# SensorSheet.net
KiCad netlist of a schematic drawn in Altium Designer
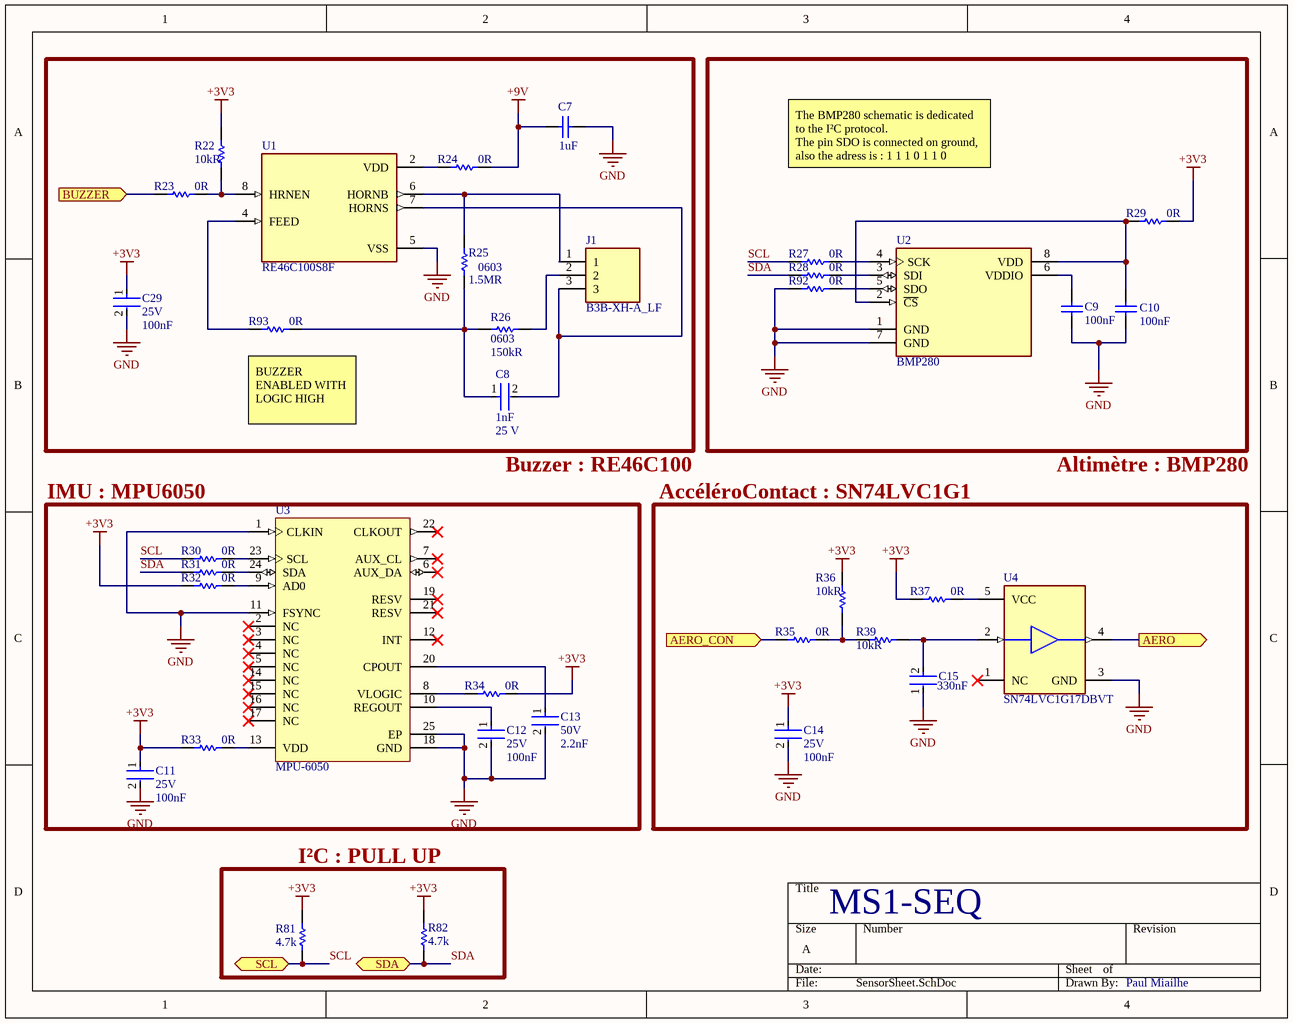
[diagram p0: SensorSheet.SchDoc]

(export (version "E")
  (design (tool "Eeschema 10.0.6"))
  (components
    (comp (ref "C7")
      (value "GRM188R61E105KA12D")
      (footprint "CAPC1608X90X35LL10T15")
      (fields
        (field (name "MANUFACTURER") "Murata")
        (field (name "CAPACITANCE") "1uF")
        (field (name "TOLERANCE") "10%")
        (field (name "VOLTAGE") "25V")
      )
      (libsource (lib "Altium Content Vault") (part "CAP"))
    )
    (comp (ref "C8")
      (value "C0603C102J3GACTU")
      (footprint "FP-C0603C-CF-MFG")
      (description "CAP CER 1000PF 25V 5% NP0 0603")
      (fields
        (field (name "OCTOPART") "https://octopart.com/c0603c102j3gactu-kemet-8375722")
        (field (name "CAPACITANCE") "1nF")
        (field (name "TOLERANCE") "0.05")
        (field (name "VOLTAGE RATING") "25 V")
      )
      (libsource (lib "Altium Content Vault") (part "b4654b650e69147ec39a6b967a45e02"))
    )
    (comp (ref "C9")
      (value "100nF")
      (footprint "SAMS-C0603-2_M")
      (description "Multi-layer Ceramic Capacitor, -55 to 125 degC, 2-Pin SMD (0603), RoHS, Tape and Reel")
      (fields (field (name "MANUFACTURER") "Samsung Electro-Mechanics"))
      (libsource (lib "Altium Content Vault") (part "CAP-NP-2"))
    )
    (comp (ref "C10")
      (value "100nF")
      (footprint "SAMS-C0603-2_M")
      (description "Multi-layer Ceramic Capacitor, -55 to 125 degC, 2-Pin SMD (0603), RoHS, Tape and Reel")
      (fields (field (name "MANUFACTURER") "Samsung Electro-Mechanics"))
      (libsource (lib "Altium Content Vault") (part "CAP-NP-2"))
    )
    (comp (ref "C11")
      (value "CGA3E2X7R1E104K080AA")
      (footprint "FP-CGA3E-0_3-0_1-MFG")
      (description "Cap Ceramic 100nF 25V X7R 10% Pad SMD 0603 +125°C Automotive T/R")
      (fields
        (field (name "VOLTAGE RATING (DC)") "25V")
        (field (name "CAPACITANCE") "100nF")
        (field (name "TOLERANCE") "10%")
        (field (name "MANUFACTURER") "TDK")
      )
      (libsource (lib "Altium Content Vault") (part "b4654b650e69147ec39a6b967a45e02"))
    )
    (comp (ref "C12")
      (value "CGA3E2X7R1E104K080AA")
      (footprint "FP-CGA3E-0_3-0_1-MFG")
      (description "Cap Ceramic 100nF 25V X7R 10% Pad SMD 0603 +125°C Automotive T/R")
      (fields
        (field (name "VOLTAGE RATING (DC)") "25V")
        (field (name "CAPACITANCE") "100nF")
        (field (name "TOLERANCE") "10%")
        (field (name "MANUFACTURER") "TDK")
      )
      (libsource (lib "Altium Content Vault") (part "b4654b650e69147ec39a6b967a45e02"))
    )
    (comp (ref "C13")
      (value "GRM1885C1H222JA01D")
      (footprint "FP-GRM188-0_1-e0_2_0_5-MFG")
      (description "Chip Multilayer Ceramic Capacitors for General Purpose, 0603, 2200pF, C0G, 30ppm/°C, 5%, 50V")
      (fields
        (field (name "VOLTAGE") "50V")
        (field (name "TOLERANCE") "5%")
        (field (name "CAPACITANCE") "2.2nF")
        (field (name "MANUFACTURER") "Murata")
      )
      (libsource (lib "Altium Content Vault") (part "11868f565c42a9108669ba33697ecf6"))
    )
    (comp (ref "C14")
      (value "CGA3E2X7R1E104K080AA")
      (footprint "FP-CGA3E-0_3-0_1-MFG")
      (description "Cap Ceramic 100nF 25V X7R 10% Pad SMD 0603 +125°C Automotive T/R")
      (fields
        (field (name "VOLTAGE RATING (DC)") "25V")
        (field (name "CAPACITANCE") "100nF")
        (field (name "TOLERANCE") "10%")
        (field (name "MANUFACTURER") "TDK")
      )
      (libsource (lib "Altium Content Vault") (part "b4654b650e69147ec39a6b967a45e02"))
    )
    (comp (ref "C15")
      (value "C1608X7R1H334K080AC")
      (footprint "FP-C1608-080-0_1-IPC_B")
      (description "Multilayer Ceramic Capacitors 330nF ±10% 50V X7R SMD 0603")
      (fields
        (field (name "CAPACITANCE") "330nF")
        (field (name "TOLERANCE") "10%")
        (field (name "VOLTAGE") "50V")
      )
      (libsource (lib "Altium Content Vault") (part "236180d848d6139a670b325ea6854c9"))
    )
    (comp (ref "C29")
      (value "CGA3E2X7R1E104K080AA")
      (footprint "FP-CGA3E-0_3-0_1-MFG")
      (description "Cap Ceramic 100nF 25V X7R 10% Pad SMD 0603 +125°C Automotive T/R")
      (fields
        (field (name "VOLTAGE RATING (DC)") "25V")
        (field (name "CAPACITANCE") "100nF")
        (field (name "TOLERANCE") "10%")
        (field (name "MANUFACTURER") "TDK")
      )
      (libsource (lib "Altium Content Vault") (part "b4654b650e69147ec39a6b967a45e02"))
    )
    (comp (ref "J1")
      (value "B3B-XH-A_LF")
      (footprint "SamacSys:B3BXHALFSN")
      (description "Connector")
      (fields (field (name "MANUFACTURER_PART_NUMBER") "B3B-XH-A(LF)(SN)"))
      (libsource (lib "*") (part "B3B-XH-A_LF__SN_"))
    )
    (comp (ref "R22")
      (value "ERJ3EKF1002V")
      (footprint "RESC1609X55X30LL15T15")
      (description "Chip Resistor, 10 KOhm, +/- 1%, 0.1 W, -55 to 155 degC, 0603 (1608 Metric), RoHS, Tape and Reel")
      (fields
        (field (name "RESISTANCE") "10kR")
        (field (name "TOLERANCE") "1%")
        (field (name "MANUFACTURER") "Panasonic")
      )
      (libsource (lib "Altium Content Vault") (part "RES-2"))
    )
    (comp (ref "R23")
      (value "0R")
      (footprint "RESC1608X55X25ML10T15")
      (description "Chip Resistor, 0 Ohm, +/- 5%, 0.1 W, -55 to 155 degC, 0603 (1608 Metric), RoHS, Tape and Reel")
      (fields (field (name "TOLERANCE") "5%") (field (name "MANUFACTURER") "Yageo"))
      (libsource (lib "Altium Content Vault") (part "RES-2"))
    )
    (comp (ref "R24")
      (value "0R")
      (footprint "RESC1608X55X25ML10T15")
      (description "Chip Resistor, 0 Ohm, +/- 5%, 0.1 W, -55 to 155 degC, 0603 (1608 Metric), RoHS, Tape and Reel")
      (fields (field (name "TOLERANCE") "5%") (field (name "MANUFACTURER") "Yageo"))
      (libsource (lib "Altium Content Vault") (part "RES-2"))
    )
    (comp (ref "R25")
      (value "ERJ-3GEYJ155V")
      (footprint "RESC1608X55X30ML15T15")
      (fields
        (field (name "MANUFACTURER") "Panasonic")
        (field (name "CASE CODE (IMPERIAL)") "0603")
        (field (name "RESISTANCE") "1.5MR")
        (field (name "TOLERANCE") "5%")
      )
      (libsource (lib "Altium Content Vault") (part "RES"))
    )
    (comp (ref "R26")
      (value "ERJ-3EKF1503V")
      (footprint "RESC1608X55X30NL15T15")
      (fields
        (field (name "MANUFACTURER") "Panasonic")
        (field (name "CASE CODE (IMPERIAL)") "0603")
        (field (name "RESISTANCE") "150kR")
        (field (name "TOLERANCE") "1%")
      )
      (libsource (lib "Altium Content Vault") (part "RES"))
    )
    (comp (ref "R27")
      (value "0R")
      (footprint "RESC1608X55X25ML10T15")
      (description "Chip Resistor, 0 Ohm, +/- 5%, 0.1 W, -55 to 155 degC, 0603 (1608 Metric), RoHS, Tape and Reel")
      (fields (field (name "TOLERANCE") "5%") (field (name "MANUFACTURER") "Yageo"))
      (libsource (lib "Altium Content Vault") (part "RES-2"))
    )
    (comp (ref "R28")
      (value "0R")
      (footprint "RESC1608X55X25ML10T15")
      (description "Chip Resistor, 0 Ohm, +/- 5%, 0.1 W, -55 to 155 degC, 0603 (1608 Metric), RoHS, Tape and Reel")
      (fields (field (name "TOLERANCE") "5%") (field (name "MANUFACTURER") "Yageo"))
      (libsource (lib "Altium Content Vault") (part "RES-2"))
    )
    (comp (ref "R29")
      (value "0R")
      (footprint "RESC1608X55X25ML10T15")
      (description "Chip Resistor, 0 Ohm, +/- 5%, 0.1 W, -55 to 155 degC, 0603 (1608 Metric), RoHS, Tape and Reel")
      (fields (field (name "TOLERANCE") "5%") (field (name "MANUFACTURER") "Yageo"))
      (libsource (lib "Altium Content Vault") (part "RES-2"))
    )
    (comp (ref "R30")
      (value "0R")
      (footprint "RESC1608X55X25ML10T15")
      (description "Chip Resistor, 0 Ohm, +/- 5%, 0.1 W, -55 to 155 degC, 0603 (1608 Metric), RoHS, Tape and Reel")
      (fields (field (name "TOLERANCE") "5%") (field (name "MANUFACTURER") "Yageo"))
      (libsource (lib "Altium Content Vault") (part "RES-2"))
    )
    (comp (ref "R31")
      (value "0R")
      (footprint "RESC1608X55X25ML10T15")
      (description "Chip Resistor, 0 Ohm, +/- 5%, 0.1 W, -55 to 155 degC, 0603 (1608 Metric), RoHS, Tape and Reel")
      (fields (field (name "TOLERANCE") "5%") (field (name "MANUFACTURER") "Yageo"))
      (libsource (lib "Altium Content Vault") (part "RES-2"))
    )
    (comp (ref "R32")
      (value "0R")
      (footprint "RESC1608X55X25ML10T15")
      (description "Chip Resistor, 0 Ohm, +/- 5%, 0.1 W, -55 to 155 degC, 0603 (1608 Metric), RoHS, Tape and Reel")
      (fields (field (name "TOLERANCE") "5%") (field (name "MANUFACTURER") "Yageo"))
      (libsource (lib "Altium Content Vault") (part "RES-2"))
    )
    (comp (ref "R33")
      (value "0R")
      (footprint "RESC1608X55X25ML10T15")
      (description "Chip Resistor, 0 Ohm, +/- 5%, 0.1 W, -55 to 155 degC, 0603 (1608 Metric), RoHS, Tape and Reel")
      (fields (field (name "TOLERANCE") "5%") (field (name "MANUFACTURER") "Yageo"))
      (libsource (lib "Altium Content Vault") (part "RES-2"))
    )
    (comp (ref "R34")
      (value "0R")
      (footprint "RESC1608X55X25ML10T15")
      (description "Chip Resistor, 0 Ohm, +/- 5%, 0.1 W, -55 to 155 degC, 0603 (1608 Metric), RoHS, Tape and Reel")
      (fields (field (name "TOLERANCE") "5%") (field (name "MANUFACTURER") "Yageo"))
      (libsource (lib "Altium Content Vault") (part "RES-2"))
    )
    (comp (ref "R35")
      (value "0R")
      (footprint "RESC1608X55X25ML10T15")
      (description "Chip Resistor, 0 Ohm, +/- 5%, 0.1 W, -55 to 155 degC, 0603 (1608 Metric), RoHS, Tape and Reel")
      (fields (field (name "TOLERANCE") "5%") (field (name "MANUFACTURER") "Yageo"))
      (libsource (lib "Altium Content Vault") (part "RES-2"))
    )
    (comp (ref "R36")
      (value "ERJ3EKF1002V")
      (footprint "RESC1609X55X30LL15T15")
      (description "Chip Resistor, 10 KOhm, +/- 1%, 0.1 W, -55 to 155 degC, 0603 (1608 Metric), RoHS, Tape and Reel")
      (fields
        (field (name "RESISTANCE") "10kR")
        (field (name "TOLERANCE") "1%")
        (field (name "MANUFACTURER") "Panasonic")
      )
      (libsource (lib "Altium Content Vault") (part "RES-2"))
    )
    (comp (ref "R37")
      (value "0R")
      (footprint "RESC1608X55X25ML10T15")
      (description "Chip Resistor, 0 Ohm, +/- 5%, 0.1 W, -55 to 155 degC, 0603 (1608 Metric), RoHS, Tape and Reel")
      (fields (field (name "TOLERANCE") "5%") (field (name "MANUFACTURER") "Yageo"))
      (libsource (lib "Altium Content Vault") (part "RES-2"))
    )
    (comp (ref "R39")
      (value "ERJ3EKF1002V")
      (footprint "RESC1609X55X30LL15T15")
      (description "Chip Resistor, 10 KOhm, +/- 1%, 0.1 W, -55 to 155 degC, 0603 (1608 Metric), RoHS, Tape and Reel")
      (fields
        (field (name "RESISTANCE") "10kR")
        (field (name "TOLERANCE") "1%")
        (field (name "MANUFACTURER") "Panasonic")
      )
      (libsource (lib "Altium Content Vault") (part "RES-2"))
    )
    (comp (ref "R81")
      (value "RC0603FR-074K7L")
      (footprint "RESC1608X55X25LL10T15")
      (description "Chip Resistor, 4.7 KOhm, +/- 1%, 0.1 W, -55 to 155 degC, 0603 (1608 Metric), RoHS, Tape and Reel")
      (fields
        (field (name "MANUFACTURER") "Yageo")
        (field (name "RESISTANCE") "4.7k")
        (field (name "TOLERANCE") "1%")
      )
      (libsource (lib "Altium Content Vault") (part "RES-2"))
    )
    (comp (ref "R82")
      (value "RC0603FR-074K7L")
      (footprint "RESC1608X55X25LL10T15")
      (description "Chip Resistor, 4.7 KOhm, +/- 1%, 0.1 W, -55 to 155 degC, 0603 (1608 Metric), RoHS, Tape and Reel")
      (fields
        (field (name "MANUFACTURER") "Yageo")
        (field (name "RESISTANCE") "4.7k")
        (field (name "TOLERANCE") "1%")
      )
      (libsource (lib "Altium Content Vault") (part "RES-2"))
    )
    (comp (ref "R92")
      (value "0R")
      (footprint "RESC1608X55X25ML10T15")
      (description "Chip Resistor, 0 Ohm, +/- 5%, 0.1 W, -55 to 155 degC, 0603 (1608 Metric), RoHS, Tape and Reel")
      (fields (field (name "TOLERANCE") "5%") (field (name "MANUFACTURER") "Yageo"))
      (libsource (lib "Altium Content Vault") (part "RES-2"))
    )
    (comp (ref "R93")
      (value "0R")
      (footprint "RESC1608X55X25ML10T15")
      (description "Chip Resistor, 0 Ohm, +/- 5%, 0.1 W, -55 to 155 degC, 0603 (1608 Metric), RoHS, Tape and Reel")
      (fields (field (name "TOLERANCE") "5%") (field (name "MANUFACTURER") "Yageo"))
      (libsource (lib "Altium Content Vault") (part "RES-2"))
    )
    (comp (ref "U1")
      (value "RE46C100S8F")
      (footprint "RE46C100S8F:SOIC127P600X175-8N")
      (fields (field (name "MF") "{'manufacturer': u'Microchip Technology'}"))
      (libsource (lib "*") (part "RE46C100S8F"))
    )
    (comp (ref "U2")
      (value "BMP280")
      (footprint "FP-BMP280-MFG")
      (description "SENSOR PRESSURE ABS")
      (libsource (lib "Altium Content Vault") (part "69b1aacbb03d82763a43fac02afba64"))
    )
    (comp (ref "U3")
      (value "MPU-6050")
      (footprint "IS-QFN-24_V")
      (fields (field (name "MANUFACTURER") "InvenSense"))
      (libsource (lib "Altium Content Vault") (part "IS-MPU-6050-QFN-24"))
    )
    (comp (ref "U4")
      (value "SN74LVC1G17DBVT")
      (footprint "FP-DBV0005A-MFG")
      (description "IC BUF NON-INVERT 5.5V SOT23-5")
      (fields
        (field (name "MANUFACTURER") "Texas Instruments")
        (field (name "OCTOPART") "https://octopart.com/sn74lvc1g17dbvt-texas+instruments-2326350")
      )
      (libsource (lib "Altium Content Vault") (part "d67d855942c6c6b24b3bb5c51ad1e18"))
    )
  )
  (nets
    (net (code "1") (name "+3V3") (class "Default")
      (node (ref "C11") (pin "1") (pinfunction "1_1") (pintype "passive"))
      (node (ref "C14") (pin "1") (pinfunction "1_1") (pintype "passive"))
      (node (ref "C29") (pin "1") (pinfunction "1_1") (pintype "passive"))
      (node (ref "R22") (pin "2") (pinfunction "2_2") (pintype "passive"))
      (node (ref "R29") (pin "2") (pinfunction "2_2") (pintype "passive"))
      (node (ref "R32") (pin "1") (pinfunction "1_1") (pintype "passive"))
      (node (ref "R33") (pin "1") (pinfunction "1_1") (pintype "passive"))
      (node (ref "R34") (pin "2") (pinfunction "2_2") (pintype "passive"))
      (node (ref "R36") (pin "2") (pinfunction "2_2") (pintype "passive"))
      (node (ref "R37") (pin "1") (pinfunction "1_1") (pintype "passive"))
      (node (ref "R81") (pin "2") (pinfunction "2_2") (pintype "passive"))
      (node (ref "R82") (pin "2") (pinfunction "2_2") (pintype "passive"))
    )
    (net (code "2") (name "+9V") (class "Default")
      (node (ref "C7") (pin "1") (pinfunction "1_1") (pintype "passive"))
      (node (ref "R24") (pin "2") (pinfunction "2_2") (pintype "passive"))
    )
    (net (code "3") (name "/AERO") (class "Default")
      (node (ref "U4") (pin "4") (pinfunction "Y_4") (pintype "output"))
    )
    (net (code "4") (name "/AERO_CON") (class "Default")
      (node (ref "R35") (pin "1") (pinfunction "1_1") (pintype "passive"))
    )
    (net (code "5") (name "/BUZZER") (class "Default")
      (node (ref "R23") (pin "1") (pinfunction "1_1") (pintype "passive"))
    )
    (net (code "6") (name "/SCL") (class "Default")
      (node (ref "R27") (pin "1") (pinfunction "1_1") (pintype "passive"))
      (node (ref "R30") (pin "1") (pinfunction "1_1") (pintype "passive"))
      (node (ref "R81") (pin "1") (pinfunction "1_1") (pintype "passive"))
    )
    (net (code "7") (name "/SDA") (class "Default")
      (node (ref "R28") (pin "1") (pinfunction "1_1") (pintype "passive"))
      (node (ref "R31") (pin "1") (pinfunction "1_1") (pintype "passive"))
      (node (ref "R82") (pin "1") (pinfunction "1_1") (pintype "passive"))
    )
    (net (code "8") (name "GND") (class "Default")
      (node (ref "C10") (pin "1") (pinfunction "1_1") (pintype "passive"))
      (node (ref "C11") (pin "2") (pinfunction "2_2") (pintype "passive"))
      (node (ref "C12") (pin "2") (pinfunction "2_2") (pintype "passive"))
      (node (ref "C13") (pin "2") (pinfunction "2_2") (pintype "passive"))
      (node (ref "C14") (pin "2") (pinfunction "2_2") (pintype "passive"))
      (node (ref "C15") (pin "1") (pinfunction "1_1") (pintype "passive"))
      (node (ref "C29") (pin "2") (pinfunction "2_2") (pintype "passive"))
      (node (ref "C7") (pin "2") (pinfunction "2_2") (pintype "passive"))
      (node (ref "C9") (pin "1") (pinfunction "1_1") (pintype "passive"))
      (node (ref "R92") (pin "1") (pinfunction "1_1") (pintype "passive"))
      (node (ref "U1") (pin "5") (pinfunction "VSS_5") (pintype "power_in"))
      (node (ref "U2") (pin "1") (pinfunction "GND_1") (pintype "power_in"))
      (node (ref "U2") (pin "7") (pinfunction "GND_7") (pintype "power_in"))
      (node (ref "U3") (pin "1") (pinfunction "CLKIN_1") (pintype "input"))
      (node (ref "U3") (pin "11") (pinfunction "FSYNC_11") (pintype "input"))
      (node (ref "U3") (pin "18") (pinfunction "GND_18") (pintype "power_in"))
      (node (ref "U3") (pin "25") (pinfunction "EP_25") (pintype "power_in"))
      (node (ref "U4") (pin "3") (pinfunction "GND_3") (pintype "power_in"))
    )
    (net (code "9") (name "Net-(C8-Pad1)") (class "Default")
      (node (ref "C8") (pin "1") (pinfunction "1_1") (pintype "passive"))
      (node (ref "R25") (pin "1") (pinfunction "1_1") (pintype "passive"))
      (node (ref "R26") (pin "1") (pinfunction "1_1") (pintype "passive"))
      (node (ref "R93") (pin "2") (pinfunction "2_2") (pintype "passive"))
    )
    (net (code "10") (name "Net-(J1-Pad2)") (class "Default")
      (node (ref "J1") (pin "2") (pinfunction "2_2") (pintype "passive"))
      (node (ref "R26") (pin "2") (pinfunction "2_2") (pintype "passive"))
    )
    (net (code "11") (name "Net-(R35-Pad2)") (class "Default")
      (node (ref "R35") (pin "2") (pinfunction "2_2") (pintype "passive"))
      (node (ref "R36") (pin "1") (pinfunction "1_1") (pintype "passive"))
      (node (ref "R39") (pin "2") (pinfunction "2_2") (pintype "passive"))
    )
    (net (code "12") (name "Net-(U1-FEED)") (class "Default")
      (node (ref "R93") (pin "1") (pinfunction "1_1") (pintype "passive"))
      (node (ref "U1") (pin "4") (pinfunction "FEED_4") (pintype "input"))
    )
    (net (code "13") (name "Net-(U1-HORNB)") (class "Default")
      (node (ref "J1") (pin "1") (pinfunction "1_1") (pintype "passive"))
      (node (ref "R25") (pin "2") (pinfunction "2_2") (pintype "passive"))
      (node (ref "U1") (pin "6") (pinfunction "HORNB_6") (pintype "output"))
    )
    (net (code "14") (name "Net-(U1-HORNS)") (class "Default")
      (node (ref "C8") (pin "2") (pinfunction "2_2") (pintype "passive"))
      (node (ref "J1") (pin "3") (pinfunction "3_3") (pintype "passive"))
      (node (ref "U1") (pin "7") (pinfunction "HORNS_7") (pintype "output"))
    )
    (net (code "15") (name "Net-(U1-HRNEN)") (class "Default")
      (node (ref "R22") (pin "1") (pinfunction "1_1") (pintype "passive"))
      (node (ref "R23") (pin "2") (pinfunction "2_2") (pintype "passive"))
      (node (ref "U1") (pin "8") (pinfunction "HRNEN_8") (pintype "input"))
    )
    (net (code "16") (name "Net-(U1-VDD)") (class "Default")
      (node (ref "R24") (pin "1") (pinfunction "1_1") (pintype "passive"))
      (node (ref "U1") (pin "2") (pinfunction "VDD_2") (pintype "power_in"))
    )
    (net (code "17") (name "Net-(U2-SCK)") (class "Default")
      (node (ref "R27") (pin "2") (pinfunction "2_2") (pintype "passive"))
      (node (ref "U2") (pin "4") (pinfunction "SCK_4") (pintype "input"))
    )
    (net (code "18") (name "Net-(U2-SDI)") (class "Default")
      (node (ref "R28") (pin "2") (pinfunction "2_2") (pintype "passive"))
      (node (ref "U2") (pin "3") (pinfunction "SDI_3") (pintype "bidirectional"))
    )
    (net (code "19") (name "Net-(U2-SDO)") (class "Default")
      (node (ref "R92") (pin "2") (pinfunction "2_2") (pintype "passive"))
      (node (ref "U2") (pin "5") (pinfunction "SDO_5") (pintype "bidirectional"))
    )
    (net (code "20") (name "Net-(U2-VDD)") (class "Default")
      (node (ref "C10") (pin "2") (pinfunction "2_2") (pintype "passive"))
      (node (ref "R29") (pin "1") (pinfunction "1_1") (pintype "passive"))
      (node (ref "U2") (pin "2") (pinfunction "~{CS}_2") (pintype "input"))
      (node (ref "U2") (pin "8") (pinfunction "VDD_8") (pintype "power_in"))
    )
    (net (code "21") (name "Net-(U2-VDDIO)") (class "Default")
      (node (ref "C9") (pin "2") (pinfunction "2_2") (pintype "passive"))
      (node (ref "U2") (pin "6") (pinfunction "VDDIO_6") (pintype "power_in"))
    )
    (net (code "22") (name "Net-(U3-AD0)") (class "Default")
      (node (ref "R32") (pin "2") (pinfunction "2_2") (pintype "passive"))
      (node (ref "U3") (pin "9") (pinfunction "AD0_9") (pintype "input"))
    )
    (net (code "23") (name "Net-(U3-CPOUT)") (class "Default")
      (node (ref "C13") (pin "1") (pinfunction "1_1") (pintype "passive"))
      (node (ref "U3") (pin "20") (pinfunction "CPOUT_20") (pintype "passive"))
    )
    (net (code "24") (name "Net-(U3-REGOUT)") (class "Default")
      (node (ref "C12") (pin "1") (pinfunction "1_1") (pintype "passive"))
      (node (ref "U3") (pin "10") (pinfunction "REGOUT_10") (pintype "passive"))
    )
    (net (code "25") (name "Net-(U3-SCL)") (class "Default")
      (node (ref "R30") (pin "2") (pinfunction "2_2") (pintype "passive"))
      (node (ref "U3") (pin "23") (pinfunction "SCL_23") (pintype "input"))
    )
    (net (code "26") (name "Net-(U3-SDA)") (class "Default")
      (node (ref "R31") (pin "2") (pinfunction "2_2") (pintype "passive"))
      (node (ref "U3") (pin "24") (pinfunction "SDA_24") (pintype "bidirectional"))
    )
    (net (code "27") (name "Net-(U3-VDD)") (class "Default")
      (node (ref "R33") (pin "2") (pinfunction "2_2") (pintype "passive"))
      (node (ref "U3") (pin "13") (pinfunction "VDD_13") (pintype "power_in"))
    )
    (net (code "28") (name "Net-(U3-VLOGIC)") (class "Default")
      (node (ref "R34") (pin "1") (pinfunction "1_1") (pintype "passive"))
      (node (ref "U3") (pin "8") (pinfunction "VLOGIC_8") (pintype "power_in"))
    )
    (net (code "29") (name "Net-(U4-A)") (class "Default")
      (node (ref "C15") (pin "2") (pinfunction "2_2") (pintype "passive"))
      (node (ref "R39") (pin "1") (pinfunction "1_1") (pintype "passive"))
      (node (ref "U4") (pin "2") (pinfunction "A_2") (pintype "input"))
    )
    (net (code "30") (name "Net-(U4-VCC)") (class "Default")
      (node (ref "R37") (pin "2") (pinfunction "2_2") (pintype "passive"))
      (node (ref "U4") (pin "5") (pinfunction "VCC_5") (pintype "power_in"))
    )
    (net (code "31") (name "unconnected-(U3-AUX_CL-Pad7)") (class "Default")
      (node (ref "U3") (pin "7") (pinfunction "AUX_CL_7") (pintype "output+no_connect"))
    )
    (net (code "32") (name "unconnected-(U3-AUX_DA-Pad6)") (class "Default")
      (node (ref "U3") (pin "6") (pinfunction "AUX_DA_6") (pintype "bidirectional+no_connect"))
    )
    (net (code "33") (name "unconnected-(U3-CLKOUT-Pad22)") (class "Default")
      (node (ref "U3") (pin "22") (pinfunction "CLKOUT_22") (pintype "output+no_connect"))
    )
    (net (code "34") (name "unconnected-(U3-INT-Pad12)") (class "Default")
      (node (ref "U3") (pin "12") (pinfunction "INT_12") (pintype "open_collector+no_connect"))
    )
    (net (code "35") (name "unconnected-(U3-NC-Pad2)") (class "Default")
      (node (ref "U3") (pin "2") (pinfunction "NC_2") (pintype "passive+no_connect"))
    )
    (net (code "36") (name "unconnected-(U3-NC-Pad3)") (class "Default")
      (node (ref "U3") (pin "3") (pinfunction "NC_3") (pintype "passive+no_connect"))
    )
    (net (code "37") (name "unconnected-(U3-NC-Pad4)") (class "Default")
      (node (ref "U3") (pin "4") (pinfunction "NC_4") (pintype "passive+no_connect"))
    )
    (net (code "38") (name "unconnected-(U3-NC-Pad5)") (class "Default")
      (node (ref "U3") (pin "5") (pinfunction "NC_5") (pintype "passive+no_connect"))
    )
    (net (code "39") (name "unconnected-(U3-NC-Pad14)") (class "Default")
      (node (ref "U3") (pin "14") (pinfunction "NC_14") (pintype "passive+no_connect"))
    )
    (net (code "40") (name "unconnected-(U3-NC-Pad15)") (class "Default")
      (node (ref "U3") (pin "15") (pinfunction "NC_15") (pintype "passive+no_connect"))
    )
    (net (code "41") (name "unconnected-(U3-NC-Pad16)") (class "Default")
      (node (ref "U3") (pin "16") (pinfunction "NC_16") (pintype "passive+no_connect"))
    )
    (net (code "42") (name "unconnected-(U3-NC-Pad17)") (class "Default")
      (node (ref "U3") (pin "17") (pinfunction "NC_17") (pintype "passive+no_connect"))
    )
    (net (code "43") (name "unconnected-(U3-RESV-Pad19)") (class "Default")
      (node (ref "U3") (pin "19") (pinfunction "RESV_19") (pintype "passive+no_connect"))
    )
    (net (code "44") (name "unconnected-(U3-RESV-Pad21)") (class "Default")
      (node (ref "U3") (pin "21") (pinfunction "RESV_21") (pintype "passive+no_connect"))
    )
    (net (code "45") (name "unconnected-(U4-NC-Pad1)") (class "Default")
      (node (ref "U4") (pin "1") (pinfunction "NC_1") (pintype "passive+no_connect"))
    )
  )
)
